# PWR_Config.net
KiCad netlist of a schematic drawn in Altium Designer
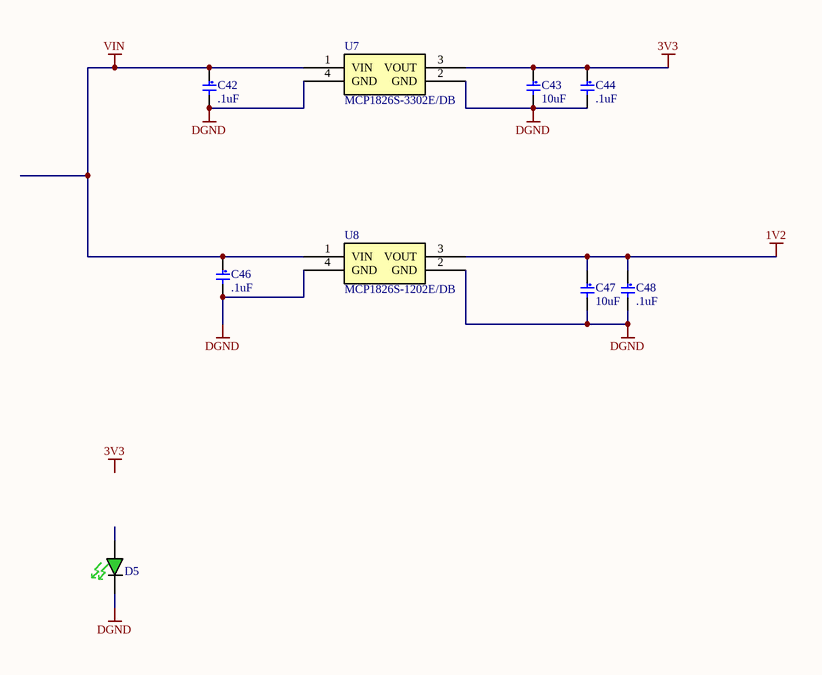
[diagram p0: PWR_Config.SchDoc]

(export (version "E")
  (design (tool "Eeschema 10.0.6"))
  (components
    (comp (ref "C42")
      (value ".1uF")
      (footprint "C0603")
      (description "CAP CER .1UF 50V 10% X7R 0603")
      (fields
        (field (name "MANUFACTURER") "Murata Electronics North America")
        (field (name "MANUFACTURER PART NUMBER") "GRM188R71H104KA93D")
      )
      (libsource (lib "myGeneral") (part "Cap-Eli"))
    )
    (comp (ref "C43")
      (value "10uF")
      (footprint "CAPC2012X06N-0805")
      (description "CAP CER .1UF 50V 10% X7R 0603")
      (fields
        (field (name "MANUFACTURER") "Murata Electronics North America")
        (field (name "MANUFACTURER PART NUMBER") "GRM188R71H104KA93D")
      )
      (libsource (lib "myGeneral") (part "Cap-Eli"))
    )
    (comp (ref "C44")
      (value ".1uF")
      (footprint "C0603")
      (description "CAP CER .1UF 50V 10% X7R 0603")
      (fields
        (field (name "MANUFACTURER") "Murata Electronics North America")
        (field (name "MANUFACTURER PART NUMBER") "GRM188R71H104KA93D")
      )
      (libsource (lib "myGeneral") (part "Cap-Eli"))
    )
    (comp (ref "C46")
      (value ".1uF")
      (footprint "C0603")
      (description "CAP CER .1UF 50V 10% X7R 0603")
      (fields
        (field (name "MANUFACTURER") "Murata Electronics North America")
        (field (name "MANUFACTURER PART NUMBER") "GRM188R71H104KA93D")
      )
      (libsource (lib "myGeneral") (part "Cap-Eli"))
    )
    (comp (ref "C47")
      (value "10uF")
      (footprint "CAPC2012X06N-0805")
      (description "CAP CER .1UF 50V 10% X7R 0603")
      (fields
        (field (name "MANUFACTURER") "Murata Electronics North America")
        (field (name "MANUFACTURER PART NUMBER") "GRM188R71H104KA93D")
      )
      (libsource (lib "myGeneral") (part "Cap-Eli"))
    )
    (comp (ref "C48")
      (value ".1uF")
      (footprint "C0603")
      (description "CAP CER .1UF 50V 10% X7R 0603")
      (fields
        (field (name "MANUFACTURER") "Murata Electronics North America")
        (field (name "MANUFACTURER PART NUMBER") "GRM188R71H104KA93D")
      )
      (libsource (lib "myGeneral") (part "Cap-Eli"))
    )
    (comp (ref "D5")
      (value "APT1608CGCK")
      (footprint "DIOM1608X08N_0603_A-C")
      (description "LED 1.6X0.8MM 570NM GRN CLR SMD")
      (fields (field (name "MANUFACTURER") "Kingbright Corp"))
      (libsource (lib "my_parts_110901") (part "LED_GREEN"))
    )
    (comp (ref "U7")
      (value "MCP1826S-3302E/DB")
      (footprint "SOT223")
      (description "IC LDO REG 1A 3.3V SOT223-3")
      (fields (field (name "MANUFACTURER") "Microchip Technology"))
      (libsource (lib "eIC") (part "MCP1826S-3302E/DB"))
    )
    (comp (ref "U8")
      (value "MCP1826S-1202E/DB")
      (footprint "SOT223")
      (description "IC LDO REG 1A 1.2V SOT223-3")
      (fields (field (name "MANUFACTURER") "Microchip Technology"))
      (libsource (lib "eIC") (part "MCP1826S-1202E/DB"))
    )
  )
  (nets
    (net (code "1") (name "1V2") (class "Default")
      (node (ref "C47") (pin "1") (pinfunction "1_1") (pintype "passive"))
      (node (ref "C48") (pin "1") (pinfunction "1_1") (pintype "passive"))
      (node (ref "U8") (pin "3") (pinfunction "VOUT_3") (pintype "passive"))
    )
    (net (code "2") (name "3V3") (class "Default")
      (node (ref "C43") (pin "1") (pinfunction "1_1") (pintype "passive"))
      (node (ref "C44") (pin "1") (pinfunction "1_1") (pintype "passive"))
      (node (ref "U7") (pin "3") (pinfunction "VOUT_3") (pintype "passive"))
    )
    (net (code "3") (name "DGND") (class "Default")
      (node (ref "C42") (pin "2") (pinfunction "2_2") (pintype "passive"))
      (node (ref "C43") (pin "2") (pinfunction "2_2") (pintype "passive"))
      (node (ref "C44") (pin "2") (pinfunction "2_2") (pintype "passive"))
      (node (ref "C46") (pin "2") (pinfunction "2_2") (pintype "passive"))
      (node (ref "C47") (pin "2") (pinfunction "2_2") (pintype "passive"))
      (node (ref "C48") (pin "2") (pinfunction "2_2") (pintype "passive"))
      (node (ref "D5") (pin "C") (pinfunction "C_C") (pintype "passive"))
      (node (ref "U7") (pin "2") (pinfunction "GND_2") (pintype "passive"))
      (node (ref "U7") (pin "4") (pinfunction "GND_4") (pintype "passive"))
      (node (ref "U8") (pin "2") (pinfunction "GND_2") (pintype "passive"))
      (node (ref "U8") (pin "4") (pinfunction "GND_4") (pintype "passive"))
    )
    (net (code "4") (name "VIN") (class "Default")
      (node (ref "C42") (pin "1") (pinfunction "1_1") (pintype "passive"))
      (node (ref "C46") (pin "1") (pinfunction "1_1") (pintype "passive"))
      (node (ref "U7") (pin "1") (pinfunction "VIN_1") (pintype "passive"))
      (node (ref "U8") (pin "1") (pinfunction "VIN_1") (pintype "passive"))
    )
    (net (code "5") (name "unconnected-(D5-PadA)") (class "Default")
      (node (ref "D5") (pin "A") (pinfunction "A_A") (pintype "passive"))
    )
  )
)
